# GloveMouse.net
KiCad netlist of a schematic drawn in EAGLE
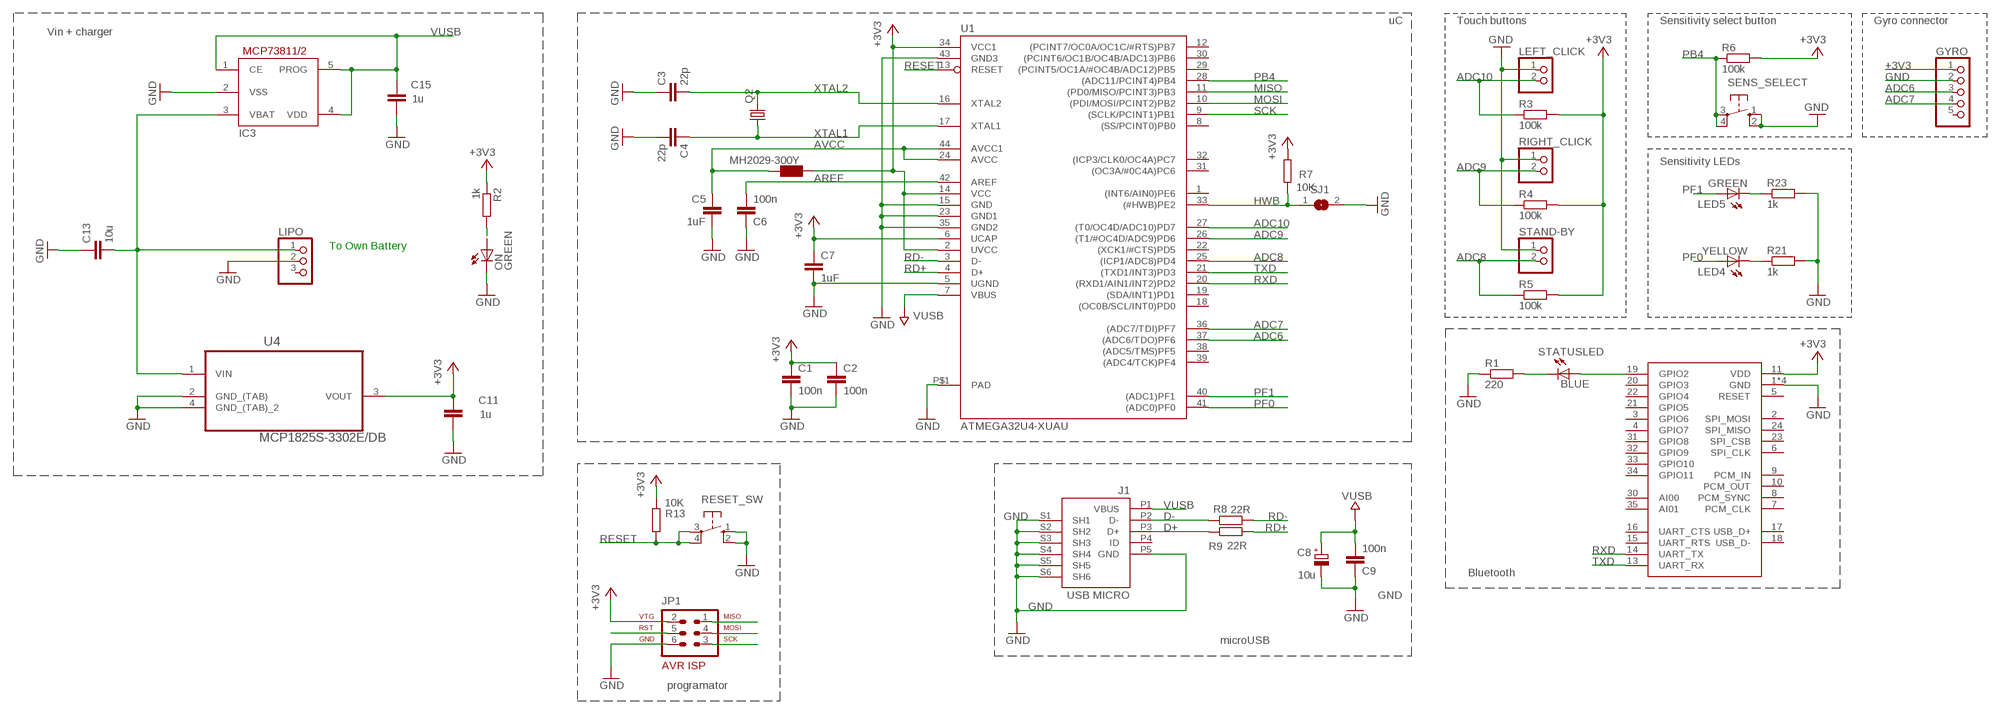
[diagram p0: schematic, sheet 1]

(export (version "E")
  (design (tool "Eeschema 10.0.6"))
  (components
    (comp (ref "C1")
      (value "100n")
      (footprint "eagle-import:C0603-ROUND")
      (libsource (lib "eagle-import") (part "C-EUC0603"))
    )
    (comp (ref "C2")
      (value "100n")
      (footprint "eagle-import:C0603-ROUND")
      (libsource (lib "eagle-import") (part "C-EUC0603"))
    )
    (comp (ref "C3")
      (value "22p")
      (footprint "eagle-import:C0603-ROUND")
      (libsource (lib "eagle-import") (part "C-EUC0603"))
    )
    (comp (ref "C4")
      (value "22p")
      (footprint "eagle-import:C0603-ROUND")
      (libsource (lib "eagle-import") (part "C-EUC0603"))
    )
    (comp (ref "C5")
      (value "1uF")
      (footprint "eagle-import:C0603-ROUND")
      (libsource (lib "eagle-import") (part "C-EUC0603"))
    )
    (comp (ref "C6")
      (value "100n")
      (footprint "eagle-import:C0603-ROUND")
      (libsource (lib "eagle-import") (part "C-EUC0603"))
    )
    (comp (ref "C7")
      (value "1uF")
      (footprint "eagle-import:C0603-ROUND")
      (libsource (lib "eagle-import") (part "C-EUC0603"))
    )
    (comp (ref "C8")
      (value "10u")
      (footprint "eagle-import:SMC_B")
      (libsource (lib "eagle-import") (part "CPOL-EUSMCB"))
    )
    (comp (ref "C9")
      (value "100n")
      (footprint "eagle-import:C0603-ROUND")
      (libsource (lib "eagle-import") (part "C-EUC0603"))
    )
    (comp (ref "C11")
      (value "1u")
      (footprint "eagle-import:C0603-ROUND")
      (libsource (lib "eagle-import") (part "C-EUC0603"))
    )
    (comp (ref "C13")
      (value "10u")
      (footprint "eagle-import:C0603")
      (libsource (lib "eagle-import") (part "rcl_C-EUC0603"))
    )
    (comp (ref "C15")
      (value "1u")
      (footprint "eagle-import:C0603-ROUND")
      (libsource (lib "eagle-import") (part "C-EUC0603"))
    )
    (comp (ref "GYRO")
      (value "PINHD-1X5")
      (footprint "eagle-import:1X05")
      (libsource (lib "eagle-import") (part "PINHD-1X5"))
    )
    (comp (ref "IC3")
      (value "MCP73811/2")
      (footprint "eagle-import:SOT23-5L")
      (libsource (lib "eagle-import") (part "MCP73811/2"))
    )
    (comp (ref "J1")
      (value "USB MICRO")
      (footprint "eagle-import:CON2_USB_MICRO_B_AT")
      (libsource (lib "eagle-import") (part "MYCON2_USB-MINI-B"))
    )
    (comp (ref "JP1")
      (value "AVR-ISP-6")
      (footprint "eagle-import:AVR-ISP-6")
      (libsource (lib "eagle-import") (part "AVR-ISP-6"))
    )
    (comp (ref "L1")
      (value "MH2029-300Y")
      (footprint "eagle-import:0805")
      (libsource (lib "eagle-import") (part "WE-CBF_0805"))
    )
    (comp (ref "LED4")
      (value "YELLOW")
      (footprint "eagle-import:CHIP-LED0805")
      (libsource (lib "eagle-import") (part "LEDCHIP-LED0805"))
    )
    (comp (ref "LED5")
      (value "GREEN")
      (footprint "eagle-import:CHIP-LED0805")
      (libsource (lib "eagle-import") (part "LEDCHIP-LED0805"))
    )
    (comp (ref "LEFT_CLICK")
      (value "PINHD-1X2")
      (footprint "eagle-import:1X02")
      (libsource (lib "eagle-import") (part "PINHD-1X2"))
    )
    (comp (ref "LIPO")
      (value "PINHD-1X3")
      (footprint "eagle-import:1X03")
      (libsource (lib "eagle-import") (part "PINHD-1X3"))
    )
    (comp (ref "ON")
      (value "GREEN")
      (footprint "eagle-import:CHIP-LED0805")
      (libsource (lib "eagle-import") (part "LEDCHIP-LED0805"))
    )
    (comp (ref "Q2")
      (value "CRYSTALCTS406")
      (footprint "eagle-import:CTS406")
      (libsource (lib "eagle-import") (part "CRYSTALCTS406"))
    )
    (comp (ref "R1")
      (value "220")
      (footprint "eagle-import:R0603")
      (libsource (lib "eagle-import") (part "resistor_R-EU_R0603"))
    )
    (comp (ref "R2")
      (value "1k")
      (footprint "eagle-import:R0603")
      (libsource (lib "eagle-import") (part "resistor_R-EU_R0603"))
    )
    (comp (ref "R3")
      (value "100k")
      (footprint "eagle-import:R0603")
      (libsource (lib "eagle-import") (part "resistor_R-EU_R0603"))
    )
    (comp (ref "R4")
      (value "100k")
      (footprint "eagle-import:R0603")
      (libsource (lib "eagle-import") (part "resistor_R-EU_R0603"))
    )
    (comp (ref "R5")
      (value "100k")
      (footprint "eagle-import:R0603")
      (libsource (lib "eagle-import") (part "resistor_R-EU_R0603"))
    )
    (comp (ref "R6")
      (value "100k")
      (footprint "eagle-import:R0603")
      (libsource (lib "eagle-import") (part "resistor_R-EU_R0603"))
    )
    (comp (ref "R7")
      (value "10K")
      (footprint "eagle-import:R0603-ROUND")
      (libsource (lib "eagle-import") (part "R-EU_R0603"))
    )
    (comp (ref "R8")
      (value "22R")
      (footprint "eagle-import:R0603-ROUND")
      (libsource (lib "eagle-import") (part "R-EU_R0603"))
    )
    (comp (ref "R9")
      (value "22R")
      (footprint "eagle-import:R0603-ROUND")
      (libsource (lib "eagle-import") (part "R-EU_R0603"))
    )
    (comp (ref "R13")
      (value "10K")
      (footprint "eagle-import:R0603-ROUND")
      (libsource (lib "eagle-import") (part "R-EU_R0603"))
    )
    (comp (ref "R21")
      (value "1k")
      (footprint "eagle-import:R0603")
      (libsource (lib "eagle-import") (part "resistor_R-EU_R0603"))
    )
    (comp (ref "R23")
      (value "1k")
      (footprint "eagle-import:R0603")
      (libsource (lib "eagle-import") (part "resistor_R-EU_R0603"))
    )
    (comp (ref "RESET_SW")
      (value "10-XX")
      (footprint "eagle-import:B3F-10XX")
      (fields (field (name "MPN") "B3F-1000"))
      (libsource (lib "eagle-import") (part "10-XX"))
    )
    (comp (ref "RIGHT_CLICK")
      (value "PINHD-1X2")
      (footprint "eagle-import:1X02")
      (libsource (lib "eagle-import") (part "PINHD-1X2"))
    )
    (comp (ref "SENS_SELECT")
      (value "10-XX")
      (footprint "eagle-import:B3F-10XX")
      (fields (field (name "MPN") "B3F-1000"))
      (libsource (lib "eagle-import") (part "10-XX"))
    )
    (comp (ref "SJ1") (value "SJ") (footprint "eagle-import:SJ") (libsource (lib "eagle-import") (part "SJ")))
    (comp (ref "STAND-BY")
      (value "PINHD-1X2")
      (footprint "eagle-import:1X02")
      (libsource (lib "eagle-import") (part "PINHD-1X2"))
    )
    (comp (ref "STATUSLED")
      (value "BLUE")
      (footprint "eagle-import:CHIP-LED0805")
      (libsource (lib "eagle-import") (part "LEDCHIP-LED0805"))
    )
    (comp (ref "U$1")
      (value "RN42")
      (footprint "eagle-import:RN42")
      (libsource (lib "eagle-import") (part "RN42"))
    )
    (comp (ref "U1")
      (value "ATMEGA32U4-XUAU")
      (footprint "eagle-import:TQFP44-PAD")
      (libsource (lib "eagle-import") (part "ATMEGA32U4-XUAU"))
    )
    (comp (ref "U4")
      (value "MCP1825S-3302E/DB")
      (footprint "eagle-import:SOT230P700X180-4N")
      (libsource (lib "eagle-import") (part "MCP1825S-3302E/DB"))
    )
  )
  (nets
    (net (code "1") (name "+3V3") (class "Default")
      (node (ref "C1") (pin "1") (pinfunction "1_1") (pintype "passive"))
      (node (ref "C11") (pin "2") (pinfunction "2_2") (pintype "passive"))
      (node (ref "C2") (pin "1") (pinfunction "1_1") (pintype "passive"))
      (node (ref "C7") (pin "1") (pinfunction "1_1") (pintype "passive"))
      (node (ref "GYRO") (pin "1") (pinfunction "1_1") (pintype "passive"))
      (node (ref "JP1") (pin "2") (pinfunction "2_2") (pintype "passive"))
      (node (ref "L1") (pin "1") (pinfunction "1_1") (pintype "passive"))
      (node (ref "R13") (pin "2") (pinfunction "2_2") (pintype "passive"))
      (node (ref "R2") (pin "1") (pinfunction "1_1") (pintype "passive"))
      (node (ref "R3") (pin "2") (pinfunction "2_2") (pintype "passive"))
      (node (ref "R4") (pin "2") (pinfunction "2_2") (pintype "passive"))
      (node (ref "R5") (pin "2") (pinfunction "2_2") (pintype "passive"))
      (node (ref "R6") (pin "2") (pinfunction "2_2") (pintype "passive"))
      (node (ref "R7") (pin "1") (pinfunction "1_1") (pintype "passive"))
      (node (ref "U$1") (pin "11") (pinfunction "VDD_11") (pintype "bidirectional"))
      (node (ref "U1") (pin "14") (pinfunction "VCC_14") (pintype "power_in"))
      (node (ref "U1") (pin "2") (pinfunction "UVCC_2") (pintype "power_in"))
      (node (ref "U1") (pin "34") (pinfunction "VCC1_34") (pintype "power_in"))
      (node (ref "U1") (pin "6") (pinfunction "UCAP_6") (pintype "passive"))
      (node (ref "U4") (pin "3") (pinfunction "VOUT_3") (pintype "output"))
    )
    (net (code "2") (name "/ADC6") (class "Default")
      (node (ref "GYRO") (pin "3") (pinfunction "3_3") (pintype "passive"))
      (node (ref "U1") (pin "37") (pinfunction "(ADC6/TDO)PF6_37") (pintype "bidirectional"))
    )
    (net (code "3") (name "/ADC7") (class "Default")
      (node (ref "GYRO") (pin "4") (pinfunction "4_4") (pintype "passive"))
      (node (ref "U1") (pin "36") (pinfunction "(ADC7/TDI)PF7_36") (pintype "bidirectional"))
    )
    (net (code "4") (name "/ADC8") (class "Default")
      (node (ref "R5") (pin "1") (pinfunction "1_1") (pintype "passive"))
      (node (ref "STAND-BY") (pin "2") (pinfunction "2_2") (pintype "passive"))
      (node (ref "U1") (pin "25") (pinfunction "(ICP1/ADC8)PD4_25") (pintype "bidirectional"))
    )
    (net (code "5") (name "/ADC9") (class "Default")
      (node (ref "R4") (pin "1") (pinfunction "1_1") (pintype "passive"))
      (node (ref "RIGHT_CLICK") (pin "2") (pinfunction "2_2") (pintype "passive"))
      (node (ref "U1") (pin "26") (pinfunction "(T1/#OC4D/ADC9)PD6_26") (pintype "bidirectional"))
    )
    (net (code "6") (name "/ADC10") (class "Default")
      (node (ref "LEFT_CLICK") (pin "2") (pinfunction "2_2") (pintype "passive"))
      (node (ref "R3") (pin "1") (pinfunction "1_1") (pintype "passive"))
      (node (ref "U1") (pin "27") (pinfunction "(T0/OC4D/ADC10)PD7_27") (pintype "bidirectional"))
    )
    (net (code "7") (name "/AREF") (class "Default")
      (node (ref "C6") (pin "2") (pinfunction "2_2") (pintype "passive"))
      (node (ref "U1") (pin "42") (pinfunction "AREF_42") (pintype "power_in"))
    )
    (net (code "8") (name "/AVCC") (class "Default")
      (node (ref "C5") (pin "1") (pinfunction "1_1") (pintype "passive"))
      (node (ref "L1") (pin "2") (pinfunction "2_2") (pintype "passive"))
      (node (ref "U1") (pin "24") (pinfunction "AVCC_24") (pintype "power_in"))
      (node (ref "U1") (pin "44") (pinfunction "AVCC1_44") (pintype "power_in"))
    )
    (net (code "9") (name "/D+") (class "Default")
      (node (ref "J1") (pin "P3") (pinfunction "D+_P3") (pintype "bidirectional"))
      (node (ref "R9") (pin "1") (pinfunction "1_1") (pintype "passive"))
    )
    (net (code "10") (name "/D-") (class "Default")
      (node (ref "J1") (pin "P2") (pinfunction "D-_P2") (pintype "bidirectional"))
      (node (ref "R8") (pin "1") (pinfunction "1_1") (pintype "passive"))
    )
    (net (code "11") (name "/HWB") (class "Default")
      (node (ref "R7") (pin "2") (pinfunction "2_2") (pintype "passive"))
      (node (ref "SJ1") (pin "1") (pinfunction "1_1") (pintype "passive"))
      (node (ref "U1") (pin "33") (pinfunction "(#HWB)PE2_33") (pintype "bidirectional"))
    )
    (net (code "12") (name "/MISO") (class "Default")
      (node (ref "JP1") (pin "1") (pinfunction "1_1") (pintype "passive"))
      (node (ref "U1") (pin "11") (pinfunction "(PD0/MISO/PCINT3)PB3_11") (pintype "bidirectional"))
    )
    (net (code "13") (name "/MOSI") (class "Default")
      (node (ref "JP1") (pin "4") (pinfunction "4_4") (pintype "passive"))
      (node (ref "U1") (pin "10") (pinfunction "(PDI/MOSI/PCINT2)PB2_10") (pintype "bidirectional"))
    )
    (net (code "14") (name "/PB4") (class "Default")
      (node (ref "R6") (pin "1") (pinfunction "1_1") (pintype "passive"))
      (node (ref "SENS_SELECT") (pin "3") (pinfunction "P_3") (pintype "passive"))
      (node (ref "SENS_SELECT") (pin "4") (pinfunction "P1_4") (pintype "passive"))
      (node (ref "U1") (pin "28") (pinfunction "(ADC11/PCINT4)PB4_28") (pintype "bidirectional"))
    )
    (net (code "15") (name "/PF0") (class "Default")
      (node (ref "LED4") (pin "A") (pinfunction "A_A") (pintype "passive"))
      (node (ref "U1") (pin "41") (pinfunction "(ADC0)PF0_41") (pintype "bidirectional"))
    )
    (net (code "16") (name "/PF1") (class "Default")
      (node (ref "LED5") (pin "A") (pinfunction "A_A") (pintype "passive"))
      (node (ref "U1") (pin "40") (pinfunction "(ADC1)PF1_40") (pintype "bidirectional"))
    )
    (net (code "17") (name "/RD+") (class "Default")
      (node (ref "R9") (pin "2") (pinfunction "2_2") (pintype "passive"))
      (node (ref "U1") (pin "4") (pinfunction "D+_4") (pintype "bidirectional"))
    )
    (net (code "18") (name "/RD-") (class "Default")
      (node (ref "R8") (pin "2") (pinfunction "2_2") (pintype "passive"))
      (node (ref "U1") (pin "3") (pinfunction "D-_3") (pintype "bidirectional"))
    )
    (net (code "19") (name "/RESET") (class "Default")
      (node (ref "JP1") (pin "5") (pinfunction "5_5") (pintype "passive"))
      (node (ref "R13") (pin "1") (pinfunction "1_1") (pintype "passive"))
      (node (ref "RESET_SW") (pin "3") (pinfunction "P_3") (pintype "passive"))
      (node (ref "RESET_SW") (pin "4") (pinfunction "P1_4") (pintype "passive"))
      (node (ref "U1") (pin "13") (pinfunction "RESET_13") (pintype "input"))
    )
    (net (code "20") (name "/RXD") (class "Default")
      (node (ref "U$1") (pin "14") (pinfunction "UART_TX_14") (pintype "bidirectional"))
      (node (ref "U1") (pin "20") (pinfunction "(RXD1/AIN1/INT2)PD2_20") (pintype "bidirectional"))
    )
    (net (code "21") (name "/SCK") (class "Default")
      (node (ref "JP1") (pin "3") (pinfunction "3_3") (pintype "passive"))
      (node (ref "U1") (pin "9") (pinfunction "(SCLK/PCINT1)PB1_9") (pintype "bidirectional"))
    )
    (net (code "22") (name "/TXD") (class "Default")
      (node (ref "U$1") (pin "13") (pinfunction "UART_RX_13") (pintype "bidirectional"))
      (node (ref "U1") (pin "21") (pinfunction "(TXD1/INT3)PD3_21") (pintype "bidirectional"))
    )
    (net (code "23") (name "/XTAL1") (class "Default")
      (node (ref "C4") (pin "1") (pinfunction "1_1") (pintype "passive"))
      (node (ref "Q2") (pin "1") (pinfunction "1_1") (pintype "passive"))
      (node (ref "U1") (pin "17") (pinfunction "XTAL1_17") (pintype "bidirectional"))
    )
    (net (code "24") (name "/XTAL2") (class "Default")
      (node (ref "C3") (pin "2") (pinfunction "2_2") (pintype "passive"))
      (node (ref "Q2") (pin "3") (pinfunction "2_3") (pintype "passive"))
      (node (ref "U1") (pin "16") (pinfunction "XTAL2_16") (pintype "bidirectional"))
    )
    (net (code "25") (name "GND") (class "Default")
      (node (ref "C1") (pin "2") (pinfunction "2_2") (pintype "passive"))
      (node (ref "C11") (pin "1") (pinfunction "1_1") (pintype "passive"))
      (node (ref "C13") (pin "1") (pinfunction "1_1") (pintype "passive"))
      (node (ref "C15") (pin "1") (pinfunction "1_1") (pintype "passive"))
      (node (ref "C2") (pin "2") (pinfunction "2_2") (pintype "passive"))
      (node (ref "C3") (pin "1") (pinfunction "1_1") (pintype "passive"))
      (node (ref "C4") (pin "2") (pinfunction "2_2") (pintype "passive"))
      (node (ref "C5") (pin "2") (pinfunction "2_2") (pintype "passive"))
      (node (ref "C6") (pin "1") (pinfunction "1_1") (pintype "passive"))
      (node (ref "C7") (pin "2") (pinfunction "2_2") (pintype "passive"))
      (node (ref "C8") (pin "-") (pinfunction "-_-") (pintype "passive"))
      (node (ref "C9") (pin "1") (pinfunction "1_1") (pintype "passive"))
      (node (ref "GYRO") (pin "2") (pinfunction "2_2") (pintype "passive"))
      (node (ref "IC3") (pin "2") (pinfunction "VSS_2") (pintype "power_in"))
      (node (ref "J1") (pin "P5") (pinfunction "GND_P5") (pintype "passive"))
      (node (ref "J1") (pin "S1") (pinfunction "SH1_S1") (pintype "passive"))
      (node (ref "J1") (pin "S2") (pinfunction "SH2_S2") (pintype "passive"))
      (node (ref "J1") (pin "S3") (pinfunction "SH3_S3") (pintype "passive"))
      (node (ref "J1") (pin "S4") (pinfunction "SH4_S4") (pintype "passive"))
      (node (ref "J1") (pin "S5") (pinfunction "SH5_S5") (pintype "passive"))
      (node (ref "J1") (pin "S6") (pinfunction "SH6_S6") (pintype "passive"))
      (node (ref "JP1") (pin "6") (pinfunction "6_6") (pintype "passive"))
      (node (ref "LEFT_CLICK") (pin "1") (pinfunction "1_1") (pintype "passive"))
      (node (ref "LIPO") (pin "2") (pinfunction "2_2") (pintype "passive"))
      (node (ref "ON") (pin "C") (pinfunction "C_C") (pintype "passive"))
      (node (ref "R1") (pin "1") (pinfunction "1_1") (pintype "passive"))
      (node (ref "R21") (pin "2") (pinfunction "2_2") (pintype "passive"))
      (node (ref "R23") (pin "2") (pinfunction "2_2") (pintype "passive"))
      (node (ref "RESET_SW") (pin "1") (pinfunction "S_1") (pintype "passive"))
      (node (ref "RESET_SW") (pin "2") (pinfunction "S1_2") (pintype "passive"))
      (node (ref "RIGHT_CLICK") (pin "1") (pinfunction "1_1") (pintype "passive"))
      (node (ref "SENS_SELECT") (pin "1") (pinfunction "S_1") (pintype "passive"))
      (node (ref "SENS_SELECT") (pin "2") (pinfunction "S1_2") (pintype "passive"))
      (node (ref "SJ1") (pin "2") (pinfunction "2_2") (pintype "passive"))
      (node (ref "STAND-BY") (pin "1") (pinfunction "1_1") (pintype "passive"))
      (node (ref "U$1") (pin "1") (pinfunction "GND_1") (pintype "bidirectional"))
      (node (ref "U$1") (pin "12") (pinfunction "GND_12") (pintype "bidirectional"))
      (node (ref "U$1") (pin "28") (pinfunction "GND_28") (pintype "bidirectional"))
      (node (ref "U$1") (pin "29") (pinfunction "GND_29") (pintype "bidirectional"))
      (node (ref "U1") (pin "15") (pinfunction "GND_15") (pintype "power_in"))
      (node (ref "U1") (pin "23") (pinfunction "GND1_23") (pintype "power_in"))
      (node (ref "U1") (pin "35") (pinfunction "GND2_35") (pintype "power_in"))
      (node (ref "U1") (pin "43") (pinfunction "GND3_43") (pintype "power_in"))
      (node (ref "U1") (pin "5") (pinfunction "UGND_5") (pintype "power_in"))
      (node (ref "U1") (pin "P$1") (pinfunction "PAD_P$1") (pintype "power_in"))
      (node (ref "U4") (pin "2") (pinfunction "GND_(TAB)_2") (pintype "passive"))
      (node (ref "U4") (pin "4") (pinfunction "GND_(TAB)_2_4") (pintype "passive"))
    )
    (net (code "26") (name "Net-(IC3-VBAT)") (class "Default")
      (node (ref "C13") (pin "2") (pinfunction "2_2") (pintype "passive"))
      (node (ref "IC3") (pin "3") (pinfunction "VBAT_3") (pintype "bidirectional"))
      (node (ref "LIPO") (pin "1") (pinfunction "1_1") (pintype "passive"))
      (node (ref "U4") (pin "1") (pinfunction "VIN_1") (pintype "input"))
    )
    (net (code "27") (name "Net-(LED4-PadC)") (class "Default")
      (node (ref "LED4") (pin "C") (pinfunction "C_C") (pintype "passive"))
      (node (ref "R21") (pin "1") (pinfunction "1_1") (pintype "passive"))
    )
    (net (code "28") (name "Net-(LED5-PadC)") (class "Default")
      (node (ref "LED5") (pin "C") (pinfunction "C_C") (pintype "passive"))
      (node (ref "R23") (pin "1") (pinfunction "1_1") (pintype "passive"))
    )
    (net (code "29") (name "Net-(ON-PadA)") (class "Default")
      (node (ref "ON") (pin "A") (pinfunction "A_A") (pintype "passive"))
      (node (ref "R2") (pin "2") (pinfunction "2_2") (pintype "passive"))
    )
    (net (code "30") (name "Net-(R1-Pad2)") (class "Default")
      (node (ref "R1") (pin "2") (pinfunction "2_2") (pintype "passive"))
      (node (ref "STATUSLED") (pin "C") (pinfunction "C_C") (pintype "passive"))
    )
    (net (code "31") (name "Net-(U$1-GPIO2)") (class "Default")
      (node (ref "STATUSLED") (pin "A") (pinfunction "A_A") (pintype "passive"))
      (node (ref "U$1") (pin "19") (pinfunction "GPIO2_19") (pintype "bidirectional"))
    )
    (net (code "32") (name "VUSB") (class "Default")
      (node (ref "C15") (pin "2") (pinfunction "2_2") (pintype "passive"))
      (node (ref "C8") (pin "+") (pinfunction "+_+") (pintype "passive"))
      (node (ref "C9") (pin "2") (pinfunction "2_2") (pintype "passive"))
      (node (ref "IC3") (pin "1") (pinfunction "CE_1") (pintype "input"))
      (node (ref "IC3") (pin "4") (pinfunction "VDD_4") (pintype "power_in"))
      (node (ref "IC3") (pin "5") (pinfunction "PROG_5") (pintype "input"))
      (node (ref "J1") (pin "P1") (pinfunction "VBUS_P1") (pintype "power_in"))
      (node (ref "U1") (pin "7") (pinfunction "VBUS_7") (pintype "input"))
    )
    (net (code "33") (name "unconnected-(GYRO-Pad5)") (class "Default")
      (node (ref "GYRO") (pin "5") (pinfunction "5_5") (pintype "passive"))
    )
    (net (code "34") (name "unconnected-(J1-ID-PadP4)") (class "Default")
      (node (ref "J1") (pin "P4") (pinfunction "ID_P4") (pintype "bidirectional"))
    )
    (net (code "35") (name "unconnected-(LIPO-Pad3)") (class "Default")
      (node (ref "LIPO") (pin "3") (pinfunction "3_3") (pintype "passive"))
    )
    (net (code "36") (name "unconnected-(U$1-AI00-Pad30)") (class "Default")
      (node (ref "U$1") (pin "30") (pinfunction "AI00_30") (pintype "bidirectional"))
    )
    (net (code "37") (name "unconnected-(U$1-AI01-Pad35)") (class "Default")
      (node (ref "U$1") (pin "35") (pinfunction "AI01_35") (pintype "bidirectional"))
    )
    (net (code "38") (name "unconnected-(U$1-GPIO3-Pad20)") (class "Default")
      (node (ref "U$1") (pin "20") (pinfunction "GPIO3_20") (pintype "bidirectional"))
    )
    (net (code "39") (name "unconnected-(U$1-GPIO4-Pad22)") (class "Default")
      (node (ref "U$1") (pin "22") (pinfunction "GPIO4_22") (pintype "bidirectional"))
    )
    (net (code "40") (name "unconnected-(U$1-GPIO5-Pad21)") (class "Default")
      (node (ref "U$1") (pin "21") (pinfunction "GPIO5_21") (pintype "bidirectional"))
    )
    (net (code "41") (name "unconnected-(U$1-GPIO6-Pad3)") (class "Default")
      (node (ref "U$1") (pin "3") (pinfunction "GPIO6_3") (pintype "bidirectional"))
    )
    (net (code "42") (name "unconnected-(U$1-GPIO7-Pad4)") (class "Default")
      (node (ref "U$1") (pin "4") (pinfunction "GPIO7_4") (pintype "bidirectional"))
    )
    (net (code "43") (name "unconnected-(U$1-GPIO8-Pad31)") (class "Default")
      (node (ref "U$1") (pin "31") (pinfunction "GPIO8_31") (pintype "bidirectional"))
    )
    (net (code "44") (name "unconnected-(U$1-GPIO9-Pad32)") (class "Default")
      (node (ref "U$1") (pin "32") (pinfunction "GPIO9_32") (pintype "bidirectional"))
    )
    (net (code "45") (name "unconnected-(U$1-GPIO10-Pad33)") (class "Default")
      (node (ref "U$1") (pin "33") (pinfunction "GPIO10_33") (pintype "bidirectional"))
    )
    (net (code "46") (name "unconnected-(U$1-GPIO11-Pad34)") (class "Default")
      (node (ref "U$1") (pin "34") (pinfunction "GPIO11_34") (pintype "bidirectional"))
    )
    (net (code "47") (name "unconnected-(U$1-PCM_CLK-Pad7)") (class "Default")
      (node (ref "U$1") (pin "7") (pinfunction "PCM_CLK_7") (pintype "bidirectional"))
    )
    (net (code "48") (name "unconnected-(U$1-PCM_IN-Pad9)") (class "Default")
      (node (ref "U$1") (pin "9") (pinfunction "PCM_IN_9") (pintype "bidirectional"))
    )
    (net (code "49") (name "unconnected-(U$1-PCM_OUT-Pad10)") (class "Default")
      (node (ref "U$1") (pin "10") (pinfunction "PCM_OUT_10") (pintype "bidirectional"))
    )
    (net (code "50") (name "unconnected-(U$1-PCM_SYNC-Pad8)") (class "Default")
      (node (ref "U$1") (pin "8") (pinfunction "PCM_SYNC_8") (pintype "bidirectional"))
    )
    (net (code "51") (name "unconnected-(U$1-RESET-Pad5)") (class "Default")
      (node (ref "U$1") (pin "5") (pinfunction "RESET_5") (pintype "bidirectional"))
    )
    (net (code "52") (name "unconnected-(U$1-SPI_CLK-Pad6)") (class "Default")
      (node (ref "U$1") (pin "6") (pinfunction "SPI_CLK_6") (pintype "bidirectional"))
    )
    (net (code "53") (name "unconnected-(U$1-SPI_CSB-Pad23)") (class "Default")
      (node (ref "U$1") (pin "23") (pinfunction "SPI_CSB_23") (pintype "bidirectional"))
    )
    (net (code "54") (name "unconnected-(U$1-SPI_MISO-Pad24)") (class "Default")
      (node (ref "U$1") (pin "24") (pinfunction "SPI_MISO_24") (pintype "bidirectional"))
    )
    (net (code "55") (name "unconnected-(U$1-SPI_MOSI-Pad2)") (class "Default")
      (node (ref "U$1") (pin "2") (pinfunction "SPI_MOSI_2") (pintype "bidirectional"))
    )
    (net (code "56") (name "unconnected-(U$1-UART_CTS-Pad16)") (class "Default")
      (node (ref "U$1") (pin "16") (pinfunction "UART_CTS_16") (pintype "bidirectional"))
    )
    (net (code "57") (name "unconnected-(U$1-UART_RTS-Pad15)") (class "Default")
      (node (ref "U$1") (pin "15") (pinfunction "UART_RTS_15") (pintype "bidirectional"))
    )
    (net (code "58") (name "unconnected-(U$1-USB_D+-Pad17)") (class "Default")
      (node (ref "U$1") (pin "17") (pinfunction "USB_D+_17") (pintype "bidirectional"))
    )
    (net (code "59") (name "unconnected-(U$1-USB_D--Pad18)") (class "Default")
      (node (ref "U$1") (pin "18") (pinfunction "USB_D-_18") (pintype "bidirectional"))
    )
    (net (code "60") (name "unconnected-(U1-(ADC4{slash}TCK)PF4-Pad39)") (class "Default")
      (node (ref "U1") (pin "39") (pinfunction "(ADC4/TCK)PF4_39") (pintype "bidirectional"))
    )
    (net (code "61") (name "unconnected-(U1-(ADC5{slash}TMS)PF5-Pad38)") (class "Default")
      (node (ref "U1") (pin "38") (pinfunction "(ADC5/TMS)PF5_38") (pintype "bidirectional"))
    )
    (net (code "62") (name "unconnected-(U1-(ICP3{slash}CLK0{slash}OC4A)PC7-Pad32)") (class "Default")
      (node (ref "U1") (pin "32") (pinfunction "(ICP3/CLK0/OC4A)PC7_32") (pintype "bidirectional"))
    )
    (net (code "63") (name "unconnected-(U1-(INT6{slash}AIN0)PE6-Pad1)") (class "Default")
      (node (ref "U1") (pin "1") (pinfunction "(INT6/AIN0)PE6_1") (pintype "bidirectional"))
    )
    (net (code "64") (name "unconnected-(U1-(OC0B{slash}SCL{slash}INT0)PD0-Pad18)") (class "Default")
      (node (ref "U1") (pin "18") (pinfunction "(OC0B/SCL/INT0)PD0_18") (pintype "bidirectional"))
    )
    (net (code "65") (name "unconnected-(U1-(OC3A{slash}#0C4A)PC6-Pad31)") (class "Default")
      (node (ref "U1") (pin "31") (pinfunction "(OC3A/#0C4A)PC6_31") (pintype "bidirectional"))
    )
    (net (code "66") (name "unconnected-(U1-(PCINT5{slash}OC1A{slash}#OC4B{slash}ADC12)PB5-Pad29)") (class "Default")
      (node (ref "U1") (pin "29") (pinfunction "(PCINT5/OC1A/#OC4B/ADC12)PB5_29") (pintype "bidirectional"))
    )
    (net (code "67") (name "unconnected-(U1-(PCINT6{slash}OC1B{slash}OC4B{slash}ADC13)PB6-Pad30)") (class "Default")
      (node (ref "U1") (pin "30") (pinfunction "(PCINT6/OC1B/OC4B/ADC13)PB6_30") (pintype "bidirectional"))
    )
    (net (code "68") (name "unconnected-(U1-(PCINT7{slash}OC0A{slash}OC1C{slash}#RTS)PB7-Pad12)") (class "Default")
      (node (ref "U1") (pin "12") (pinfunction "(PCINT7/OC0A/OC1C/#RTS)PB7_12") (pintype "bidirectional"))
    )
    (net (code "69") (name "unconnected-(U1-(SDA{slash}INT1)PD1-Pad19)") (class "Default")
      (node (ref "U1") (pin "19") (pinfunction "(SDA/INT1)PD1_19") (pintype "bidirectional"))
    )
    (net (code "70") (name "unconnected-(U1-(SS{slash}PCINT0)PB0-Pad8)") (class "Default")
      (node (ref "U1") (pin "8") (pinfunction "(SS/PCINT0)PB0_8") (pintype "bidirectional"))
    )
    (net (code "71") (name "unconnected-(U1-(XCK1{slash}#CTS)PD5-Pad22)") (class "Default")
      (node (ref "U1") (pin "22") (pinfunction "(XCK1/#CTS)PD5_22") (pintype "bidirectional"))
    )
  )
)
